# Akl-atmel.net
KiCad netlist of a schematic drawn in EAGLE
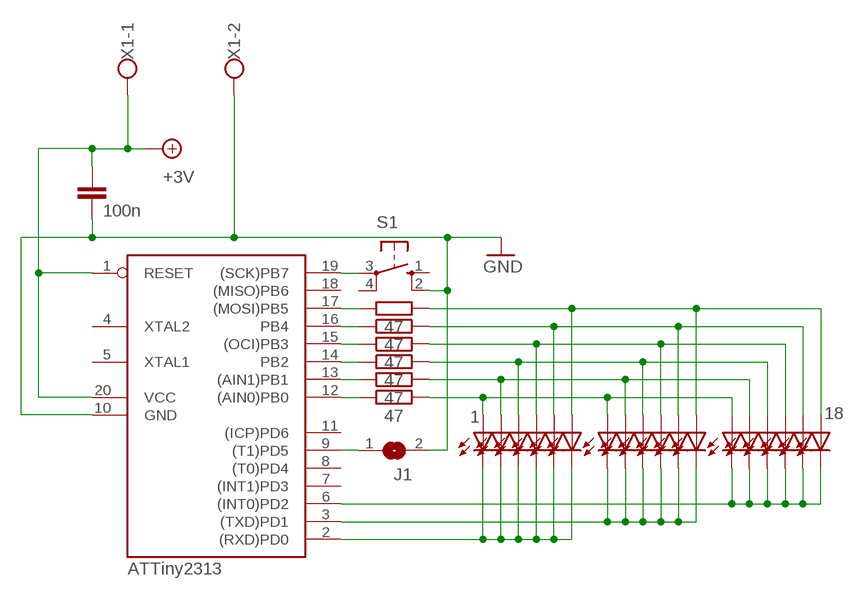
[diagram p0: schematic, sheet 1]

(export (version "E")
  (design (tool "Eeschema 10.0.6"))
  (components
    (comp (ref "C1")
      (value "100n")
      (footprint "eagle-import:C025-025X050")
      (libsource (lib "eagle-import") (part "C-EU025-025X050"))
    )
    (comp (ref "IC1")
      (value "ATTiny2313")
      (footprint "eagle-import:DIL20")
      (libsource (lib "eagle-import") (part "AT90S2313P"))
    )
    (comp (ref "J1") (value "SJ") (footprint "eagle-import:SJ") (libsource (lib "eagle-import") (part "SJ")))
    (comp (ref "LED1")
      (value "1")
      (footprint "eagle-import:LED5MM")
      (libsource (lib "eagle-import") (part "LED5MM"))
    )
    (comp (ref "LED2")
      (value "LED5MM")
      (footprint "eagle-import:LED5MM")
      (libsource (lib "eagle-import") (part "LED5MM"))
    )
    (comp (ref "LED3")
      (value "LED5MM")
      (footprint "eagle-import:LED5MM")
      (libsource (lib "eagle-import") (part "LED5MM"))
    )
    (comp (ref "LED4")
      (value "LED5MM")
      (footprint "eagle-import:LED5MM")
      (libsource (lib "eagle-import") (part "LED5MM"))
    )
    (comp (ref "LED5")
      (value "LED5MM")
      (footprint "eagle-import:LED5MM")
      (libsource (lib "eagle-import") (part "LED5MM"))
    )
    (comp (ref "LED6")
      (value "LED5MM")
      (footprint "eagle-import:LED5MM")
      (libsource (lib "eagle-import") (part "LED5MM"))
    )
    (comp (ref "LED7")
      (value "LED5MM")
      (footprint "eagle-import:LED5MM")
      (libsource (lib "eagle-import") (part "LED5MM"))
    )
    (comp (ref "LED8")
      (value "LED5MM")
      (footprint "eagle-import:LED5MM")
      (libsource (lib "eagle-import") (part "LED5MM"))
    )
    (comp (ref "LED9")
      (value "LED5MM")
      (footprint "eagle-import:LED5MM")
      (libsource (lib "eagle-import") (part "LED5MM"))
    )
    (comp (ref "LED10")
      (value "LED5MM")
      (footprint "eagle-import:LED5MM")
      (libsource (lib "eagle-import") (part "LED5MM"))
    )
    (comp (ref "LED11")
      (value "LED5MM")
      (footprint "eagle-import:LED5MM")
      (libsource (lib "eagle-import") (part "LED5MM"))
    )
    (comp (ref "LED12")
      (value "LED5MM")
      (footprint "eagle-import:LED5MM")
      (libsource (lib "eagle-import") (part "LED5MM"))
    )
    (comp (ref "LED13")
      (value "LED5MM")
      (footprint "eagle-import:LED5MM")
      (libsource (lib "eagle-import") (part "LED5MM"))
    )
    (comp (ref "LED14")
      (value "LED5MM")
      (footprint "eagle-import:LED5MM")
      (libsource (lib "eagle-import") (part "LED5MM"))
    )
    (comp (ref "LED15")
      (value "LED5MM")
      (footprint "eagle-import:LED5MM")
      (libsource (lib "eagle-import") (part "LED5MM"))
    )
    (comp (ref "LED16")
      (value "LED5MM")
      (footprint "eagle-import:LED5MM")
      (libsource (lib "eagle-import") (part "LED5MM"))
    )
    (comp (ref "LED17")
      (value "LED5MM")
      (footprint "eagle-import:LED5MM")
      (libsource (lib "eagle-import") (part "LED5MM"))
    )
    (comp (ref "LED18")
      (value "18")
      (footprint "eagle-import:LED5MM")
      (libsource (lib "eagle-import") (part "LED5MM"))
    )
    (comp (ref "R1")
      (value "47")
      (footprint "eagle-import:0207_7")
      (libsource (lib "eagle-import") (part "R-EU_0207/7"))
    )
    (comp (ref "R2")
      (value "47")
      (footprint "eagle-import:0207_7")
      (libsource (lib "eagle-import") (part "R-EU_0207/7"))
    )
    (comp (ref "R3")
      (value "47")
      (footprint "eagle-import:0207_7")
      (libsource (lib "eagle-import") (part "R-EU_0207/7"))
    )
    (comp (ref "R4")
      (value "47")
      (footprint "eagle-import:0207_7")
      (libsource (lib "eagle-import") (part "R-EU_0207/7"))
    )
    (comp (ref "R5")
      (value "47")
      (footprint "eagle-import:0207_7")
      (libsource (lib "eagle-import") (part "R-EU_0207/7"))
    )
    (comp (ref "R6")
      (value "47")
      (footprint "eagle-import:0207_7")
      (libsource (lib "eagle-import") (part "R-EU_0207/7"))
    )
    (comp (ref "S1")
      (value "10-XX")
      (footprint "eagle-import:B3F-10XX")
      (libsource (lib "eagle-import") (part "10-XX"))
    )
    (comp (ref "X1")
      (value "CON2-RIA057")
      (footprint "eagle-import:RIA_057_02")
      (libsource (lib "eagle-import") (part "CON2-RIA057"))
    )
  )
  (nets
    (net (code "1") (name "+3V") (class "Default")
      (node (ref "C1") (pin "1") (pinfunction "1_1") (pintype "passive"))
      (node (ref "IC1") (pin "1") (pinfunction "RESET_1") (pintype "bidirectional"))
      (node (ref "IC1") (pin "20") (pinfunction "VCC_20") (pintype "power_in"))
      (node (ref "X1") (pin "1") (pinfunction "KL_1") (pintype "passive"))
    )
    (net (code "2") (name "GND") (class "Default")
      (node (ref "C1") (pin "2") (pinfunction "2_2") (pintype "passive"))
      (node (ref "IC1") (pin "10") (pinfunction "GND_10") (pintype "power_in"))
      (node (ref "J1") (pin "2") (pinfunction "2_2") (pintype "passive"))
      (node (ref "S1") (pin "2") (pinfunction "S1_2") (pintype "passive"))
      (node (ref "X1") (pin "2") (pinfunction "KL_2") (pintype "passive"))
    )
    (net (code "3") (name "Net-(IC1-(AIN0)PB0)") (class "Default")
      (node (ref "IC1") (pin "12") (pinfunction "(AIN0)PB0_12") (pintype "bidirectional"))
      (node (ref "R6") (pin "1") (pinfunction "1_1") (pintype "passive"))
    )
    (net (code "4") (name "Net-(IC1-(AIN1)PB1)") (class "Default")
      (node (ref "IC1") (pin "13") (pinfunction "(AIN1)PB1_13") (pintype "bidirectional"))
      (node (ref "R5") (pin "1") (pinfunction "1_1") (pintype "passive"))
    )
    (net (code "5") (name "Net-(IC1-(INT0)PD2)") (class "Default")
      (node (ref "IC1") (pin "6") (pinfunction "(INT0)PD2_6") (pintype "bidirectional"))
      (node (ref "LED13") (pin "K") (pinfunction "C_K") (pintype "passive"))
      (node (ref "LED14") (pin "K") (pinfunction "C_K") (pintype "passive"))
      (node (ref "LED15") (pin "K") (pinfunction "C_K") (pintype "passive"))
      (node (ref "LED16") (pin "K") (pinfunction "C_K") (pintype "passive"))
      (node (ref "LED17") (pin "K") (pinfunction "C_K") (pintype "passive"))
      (node (ref "LED18") (pin "K") (pinfunction "C_K") (pintype "passive"))
    )
    (net (code "6") (name "Net-(IC1-(MOSI)PB5)") (class "Default")
      (node (ref "IC1") (pin "17") (pinfunction "(MOSI)PB5_17") (pintype "bidirectional"))
      (node (ref "R1") (pin "1") (pinfunction "1_1") (pintype "passive"))
    )
    (net (code "7") (name "Net-(IC1-(OCI)PB3)") (class "Default")
      (node (ref "IC1") (pin "15") (pinfunction "(OCI)PB3_15") (pintype "bidirectional"))
      (node (ref "R3") (pin "1") (pinfunction "1_1") (pintype "passive"))
    )
    (net (code "8") (name "Net-(IC1-(RXD)PD0)") (class "Default")
      (node (ref "IC1") (pin "2") (pinfunction "(RXD)PD0_2") (pintype "bidirectional"))
      (node (ref "LED1") (pin "K") (pinfunction "C_K") (pintype "passive"))
      (node (ref "LED2") (pin "K") (pinfunction "C_K") (pintype "passive"))
      (node (ref "LED3") (pin "K") (pinfunction "C_K") (pintype "passive"))
      (node (ref "LED4") (pin "K") (pinfunction "C_K") (pintype "passive"))
      (node (ref "LED5") (pin "K") (pinfunction "C_K") (pintype "passive"))
      (node (ref "LED6") (pin "K") (pinfunction "C_K") (pintype "passive"))
    )
    (net (code "9") (name "Net-(IC1-(SCK)PB7)") (class "Default")
      (node (ref "IC1") (pin "19") (pinfunction "(SCK)PB7_19") (pintype "bidirectional"))
      (node (ref "S1") (pin "3") (pinfunction "P_3") (pintype "passive"))
    )
    (net (code "10") (name "Net-(IC1-(T1)PD5)") (class "Default")
      (node (ref "IC1") (pin "9") (pinfunction "(T1)PD5_9") (pintype "bidirectional"))
      (node (ref "J1") (pin "1") (pinfunction "1_1") (pintype "passive"))
    )
    (net (code "11") (name "Net-(IC1-(TXD)PD1)") (class "Default")
      (node (ref "IC1") (pin "3") (pinfunction "(TXD)PD1_3") (pintype "bidirectional"))
      (node (ref "LED10") (pin "K") (pinfunction "C_K") (pintype "passive"))
      (node (ref "LED11") (pin "K") (pinfunction "C_K") (pintype "passive"))
      (node (ref "LED12") (pin "K") (pinfunction "C_K") (pintype "passive"))
      (node (ref "LED7") (pin "K") (pinfunction "C_K") (pintype "passive"))
      (node (ref "LED8") (pin "K") (pinfunction "C_K") (pintype "passive"))
      (node (ref "LED9") (pin "K") (pinfunction "C_K") (pintype "passive"))
    )
    (net (code "12") (name "Net-(IC1-PB2)") (class "Default")
      (node (ref "IC1") (pin "14") (pinfunction "PB2_14") (pintype "bidirectional"))
      (node (ref "R4") (pin "1") (pinfunction "1_1") (pintype "passive"))
    )
    (net (code "13") (name "Net-(IC1-PB4)") (class "Default")
      (node (ref "IC1") (pin "16") (pinfunction "PB4_16") (pintype "bidirectional"))
      (node (ref "R2") (pin "1") (pinfunction "1_1") (pintype "passive"))
    )
    (net (code "14") (name "Net-(LED1-PadA)") (class "Default")
      (node (ref "LED1") (pin "A") (pinfunction "A_A") (pintype "passive"))
      (node (ref "LED13") (pin "A") (pinfunction "A_A") (pintype "passive"))
      (node (ref "LED7") (pin "A") (pinfunction "A_A") (pintype "passive"))
      (node (ref "R6") (pin "2") (pinfunction "2_2") (pintype "passive"))
    )
    (net (code "15") (name "Net-(LED10-PadA)") (class "Default")
      (node (ref "LED10") (pin "A") (pinfunction "A_A") (pintype "passive"))
      (node (ref "LED16") (pin "A") (pinfunction "A_A") (pintype "passive"))
      (node (ref "LED4") (pin "A") (pinfunction "A_A") (pintype "passive"))
      (node (ref "R3") (pin "2") (pinfunction "2_2") (pintype "passive"))
    )
    (net (code "16") (name "Net-(LED11-PadA)") (class "Default")
      (node (ref "LED11") (pin "A") (pinfunction "A_A") (pintype "passive"))
      (node (ref "LED17") (pin "A") (pinfunction "A_A") (pintype "passive"))
      (node (ref "LED5") (pin "A") (pinfunction "A_A") (pintype "passive"))
      (node (ref "R2") (pin "2") (pinfunction "2_2") (pintype "passive"))
    )
    (net (code "17") (name "Net-(LED12-PadA)") (class "Default")
      (node (ref "LED12") (pin "A") (pinfunction "A_A") (pintype "passive"))
      (node (ref "LED18") (pin "A") (pinfunction "A_A") (pintype "passive"))
      (node (ref "LED6") (pin "A") (pinfunction "A_A") (pintype "passive"))
      (node (ref "R1") (pin "2") (pinfunction "2_2") (pintype "passive"))
    )
    (net (code "18") (name "Net-(LED14-PadA)") (class "Default")
      (node (ref "LED14") (pin "A") (pinfunction "A_A") (pintype "passive"))
      (node (ref "LED2") (pin "A") (pinfunction "A_A") (pintype "passive"))
      (node (ref "LED8") (pin "A") (pinfunction "A_A") (pintype "passive"))
      (node (ref "R5") (pin "2") (pinfunction "2_2") (pintype "passive"))
    )
    (net (code "19") (name "Net-(LED15-PadA)") (class "Default")
      (node (ref "LED15") (pin "A") (pinfunction "A_A") (pintype "passive"))
      (node (ref "LED3") (pin "A") (pinfunction "A_A") (pintype "passive"))
      (node (ref "LED9") (pin "A") (pinfunction "A_A") (pintype "passive"))
      (node (ref "R4") (pin "2") (pinfunction "2_2") (pintype "passive"))
    )
    (net (code "20") (name "unconnected-(IC1-(ICP)PD6-Pad11)") (class "Default")
      (node (ref "IC1") (pin "11") (pinfunction "(ICP)PD6_11") (pintype "bidirectional"))
    )
    (net (code "21") (name "unconnected-(IC1-(INT1)PD3-Pad7)") (class "Default")
      (node (ref "IC1") (pin "7") (pinfunction "(INT1)PD3_7") (pintype "bidirectional"))
    )
    (net (code "22") (name "unconnected-(IC1-(MISO)PB6-Pad18)") (class "Default")
      (node (ref "IC1") (pin "18") (pinfunction "(MISO)PB6_18") (pintype "bidirectional"))
    )
    (net (code "23") (name "unconnected-(IC1-(T0)PD4-Pad8)") (class "Default")
      (node (ref "IC1") (pin "8") (pinfunction "(T0)PD4_8") (pintype "bidirectional"))
    )
    (net (code "24") (name "unconnected-(IC1-XTAL1-Pad5)") (class "Default")
      (node (ref "IC1") (pin "5") (pinfunction "XTAL1_5") (pintype "bidirectional"))
    )
    (net (code "25") (name "unconnected-(IC1-XTAL2-Pad4)") (class "Default")
      (node (ref "IC1") (pin "4") (pinfunction "XTAL2_4") (pintype "bidirectional"))
    )
    (net (code "26") (name "unconnected-(S1-P1-Pad4)") (class "Default")
      (node (ref "S1") (pin "4") (pinfunction "P1_4") (pintype "passive"))
    )
    (net (code "27") (name "unconnected-(S1-S-Pad1)") (class "Default")
      (node (ref "S1") (pin "1") (pinfunction "S_1") (pintype "passive"))
    )
  )
)
